# P2_2478.net
KiCad netlist of a schematic drawn in Altium Designer
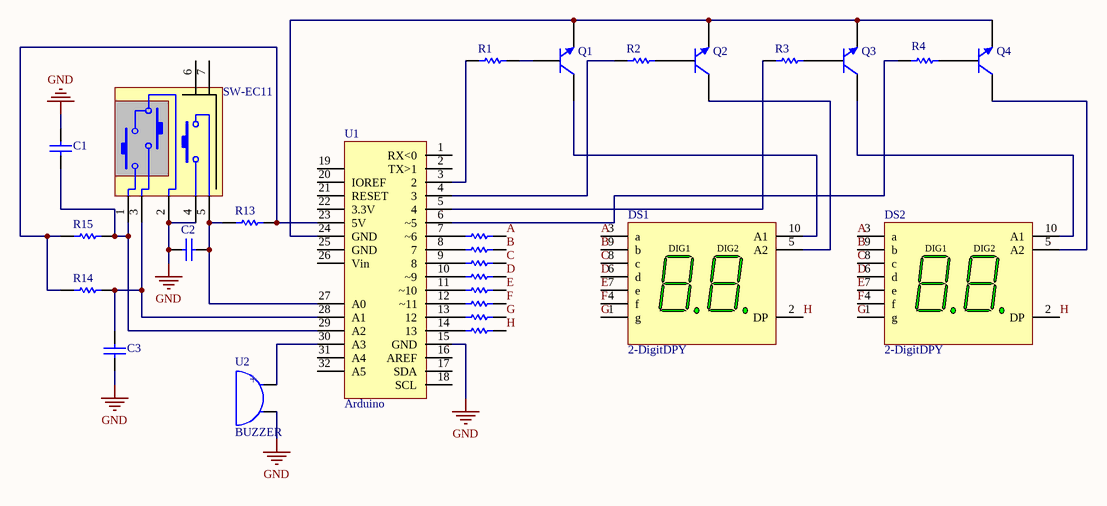
[diagram p0: P2_2478.SchDoc]

(export (version "E")
  (design (tool "Eeschema 10.0.6"))
  (components
    (comp (ref "C1")
      (value "Cap")
      (footprint "RAD-0.2")
      (description "Capacitor")
      (fields (field (name "PUBLISHER") "Altium Limited"))
      (libsource (lib "Miscellaneous Devices") (part "Cap"))
    )
    (comp (ref "C2")
      (value "Cap")
      (footprint "RAD-0.2")
      (description "Capacitor")
      (fields (field (name "PUBLISHER") "Altium Limited"))
      (libsource (lib "Miscellaneous Devices") (part "Cap"))
    )
    (comp (ref "C3")
      (value "Cap")
      (footprint "RAD-0.2")
      (description "Capacitor")
      (fields (field (name "PUBLISHER") "Altium Limited"))
      (libsource (lib "Miscellaneous Devices") (part "Cap"))
    )
    (comp (ref "DS1")
      (value "2-DigitDPY")
      (footprint "2-DigitDPY")
      (description "9.2 mm Green 7-Segment Display: 2-Digit, RH DP")
      (fields (field (name "PUBLISHER") "Altium Limited"))
      (libsource (lib "LixhSch") (part "2-DigitDPY"))
    )
    (comp (ref "DS2")
      (value "2-DigitDPY")
      (footprint "2-DigitDPY")
      (description "9.2 mm Green 7-Segment Display: 2-Digit, RH DP")
      (fields (field (name "PUBLISHER") "Altium Limited"))
      (libsource (lib "LixhSch") (part "2-DigitDPY"))
    )
    (comp (ref "Q1")
      (value "NPN")
      (footprint "TO-226")
      (description "NPN Bipolar Transistor")
      (fields (field (name "PUBLISHER") "Altium Limited"))
      (libsource (lib "Miscellaneous Devices") (part "NPN"))
    )
    (comp (ref "Q2")
      (value "NPN")
      (footprint "TO-226")
      (description "NPN Bipolar Transistor")
      (fields (field (name "PUBLISHER") "Altium Limited"))
      (libsource (lib "Miscellaneous Devices") (part "NPN"))
    )
    (comp (ref "Q3")
      (value "NPN")
      (footprint "TO-226")
      (description "NPN Bipolar Transistor")
      (fields (field (name "PUBLISHER") "Altium Limited"))
      (libsource (lib "Miscellaneous Devices") (part "NPN"))
    )
    (comp (ref "Q4")
      (value "NPN")
      (footprint "TO-226")
      (description "NPN Bipolar Transistor")
      (fields (field (name "PUBLISHER") "Altium Limited"))
      (libsource (lib "Miscellaneous Devices") (part "NPN"))
    )
    (comp (ref "R1")
      (value "Res1")
      (footprint "AXIAL-0.4")
      (description "Resistor")
      (fields (field (name "PUBLISHER") "Altium Limited"))
      (libsource (lib "Miscellaneous Devices") (part "Res1"))
    )
    (comp (ref "R2")
      (value "Res1")
      (footprint "AXIAL-0.4")
      (description "Resistor")
      (fields (field (name "PUBLISHER") "Altium Limited"))
      (libsource (lib "Miscellaneous Devices") (part "Res1"))
    )
    (comp (ref "R3")
      (value "Res1")
      (footprint "AXIAL-0.4")
      (description "Resistor")
      (fields (field (name "PUBLISHER") "Altium Limited"))
      (libsource (lib "Miscellaneous Devices") (part "Res1"))
    )
    (comp (ref "R4")
      (value "Res1")
      (footprint "AXIAL-0.4")
      (description "Resistor")
      (fields (field (name "PUBLISHER") "Altium Limited"))
      (libsource (lib "Miscellaneous Devices") (part "Res1"))
    )
    (comp (ref "R5")
      (value "Res1")
      (footprint "AXIAL-0.4")
      (description "Resistor")
      (fields (field (name "PUBLISHER") "Altium Limited"))
      (libsource (lib "Miscellaneous Devices") (part "Res1"))
    )
    (comp (ref "R6")
      (value "Res1")
      (footprint "AXIAL-0.4")
      (description "Resistor")
      (fields (field (name "PUBLISHER") "Altium Limited"))
      (libsource (lib "Miscellaneous Devices") (part "Res1"))
    )
    (comp (ref "R7")
      (value "Res1")
      (footprint "AXIAL-0.4")
      (description "Resistor")
      (fields (field (name "PUBLISHER") "Altium Limited"))
      (libsource (lib "Miscellaneous Devices") (part "Res1"))
    )
    (comp (ref "R8")
      (value "Res1")
      (footprint "AXIAL-0.4")
      (description "Resistor")
      (fields (field (name "PUBLISHER") "Altium Limited"))
      (libsource (lib "Miscellaneous Devices") (part "Res1"))
    )
    (comp (ref "R9")
      (value "Res1")
      (footprint "AXIAL-0.4")
      (description "Resistor")
      (fields (field (name "PUBLISHER") "Altium Limited"))
      (libsource (lib "Miscellaneous Devices") (part "Res1"))
    )
    (comp (ref "R10")
      (value "Res1")
      (footprint "AXIAL-0.4")
      (description "Resistor")
      (fields (field (name "PUBLISHER") "Altium Limited"))
      (libsource (lib "Miscellaneous Devices") (part "Res1"))
    )
    (comp (ref "R11")
      (value "Res1")
      (footprint "AXIAL-0.4")
      (description "Resistor")
      (fields (field (name "PUBLISHER") "Altium Limited"))
      (libsource (lib "Miscellaneous Devices") (part "Res1"))
    )
    (comp (ref "R12")
      (value "Res1")
      (footprint "AXIAL-0.4")
      (description "Resistor")
      (fields (field (name "PUBLISHER") "Altium Limited"))
      (libsource (lib "Miscellaneous Devices") (part "Res1"))
    )
    (comp (ref "R13")
      (value "Res1")
      (footprint "AXIAL-0.4")
      (description "Resistor")
      (fields (field (name "PUBLISHER") "Altium Limited"))
      (libsource (lib "Miscellaneous Devices") (part "Res1"))
    )
    (comp (ref "R14")
      (value "Res1")
      (footprint "AXIAL-0.4")
      (description "Resistor")
      (fields (field (name "PUBLISHER") "Altium Limited"))
      (libsource (lib "Miscellaneous Devices") (part "Res1"))
    )
    (comp (ref "R15")
      (value "Res1")
      (footprint "AXIAL-0.4")
      (description "Resistor")
      (fields (field (name "PUBLISHER") "Altium Limited"))
      (libsource (lib "Miscellaneous Devices") (part "Res1"))
    )
    (comp (ref "SW-EC11")
      (value "SW-EC11")
      (footprint "EC11")
      (description "旋转编码开关")
      (fields (field (name "PUBLISHER") "Altium Limited"))
      (libsource (lib "LixhSch") (part "SW-EC11"))
    )
    (comp (ref "U1")
      (value "Arduino")
      (footprint "Arduino-UNO")
      (libsource (lib "LixhSch") (part "Arduino-UNO"))
    )
    (comp (ref "U2")
      (value "BUZZER")
      (footprint "Buzzer")
      (description "Buzzer")
      (libsource (lib "Miscellaneous Devices") (part "BUZZER"))
    )
  )
  (nets
    (net (code "1") (name "/A") (class "Default")
      (node (ref "DS1") (pin "3") (pinfunction "a_3") (pintype "passive"))
      (node (ref "DS2") (pin "3") (pinfunction "a_3") (pintype "passive"))
      (node (ref "R5") (pin "2") (pinfunction "2_2") (pintype "passive"))
    )
    (net (code "2") (name "/B") (class "Default")
      (node (ref "DS1") (pin "9") (pinfunction "b_9") (pintype "passive"))
      (node (ref "DS2") (pin "9") (pinfunction "b_9") (pintype "passive"))
      (node (ref "R6") (pin "2") (pinfunction "2_2") (pintype "passive"))
    )
    (net (code "3") (name "/C") (class "Default")
      (node (ref "DS1") (pin "8") (pinfunction "c_8") (pintype "passive"))
      (node (ref "DS2") (pin "8") (pinfunction "c_8") (pintype "passive"))
      (node (ref "R7") (pin "2") (pinfunction "2_2") (pintype "passive"))
    )
    (net (code "4") (name "/D") (class "Default")
      (node (ref "DS1") (pin "6") (pinfunction "d_6") (pintype "passive"))
      (node (ref "DS2") (pin "6") (pinfunction "d_6") (pintype "passive"))
      (node (ref "R8") (pin "2") (pinfunction "2_2") (pintype "passive"))
    )
    (net (code "5") (name "/E") (class "Default")
      (node (ref "DS1") (pin "7") (pinfunction "e_7") (pintype "passive"))
      (node (ref "DS2") (pin "7") (pinfunction "e_7") (pintype "passive"))
      (node (ref "R9") (pin "2") (pinfunction "2_2") (pintype "passive"))
    )
    (net (code "6") (name "/F") (class "Default")
      (node (ref "DS1") (pin "4") (pinfunction "f_4") (pintype "passive"))
      (node (ref "DS2") (pin "4") (pinfunction "f_4") (pintype "passive"))
      (node (ref "R10") (pin "2") (pinfunction "2_2") (pintype "passive"))
    )
    (net (code "7") (name "/G") (class "Default")
      (node (ref "DS1") (pin "1") (pinfunction "g_1") (pintype "passive"))
      (node (ref "DS2") (pin "1") (pinfunction "g_1") (pintype "passive"))
      (node (ref "R11") (pin "2") (pinfunction "2_2") (pintype "passive"))
    )
    (net (code "8") (name "/H") (class "Default")
      (node (ref "DS1") (pin "2") (pinfunction "DP_2") (pintype "passive"))
      (node (ref "DS2") (pin "2") (pinfunction "DP_2") (pintype "passive"))
      (node (ref "R12") (pin "2") (pinfunction "2_2") (pintype "passive"))
    )
    (net (code "9") (name "GND") (class "Default")
      (node (ref "C1") (pin "2") (pinfunction "2_2") (pintype "passive"))
      (node (ref "C2") (pin "2") (pinfunction "2_2") (pintype "passive"))
      (node (ref "C3") (pin "2") (pinfunction "2_2") (pintype "passive"))
      (node (ref "SW-EC11") (pin "2") (pinfunction "2_2") (pintype "passive"))
      (node (ref "SW-EC11") (pin "4") (pinfunction "4_4") (pintype "passive"))
      (node (ref "U1") (pin "15") (pinfunction "GND_15") (pintype "power_in"))
      (node (ref "U2") (pin "2") (pinfunction "B_2") (pintype "passive"))
    )
    (net (code "10") (name "Net-(DS1-A1)") (class "Default")
      (node (ref "DS1") (pin "10") (pinfunction "A1_10") (pintype "passive"))
      (node (ref "Q1") (pin "1") (pinfunction "C_1") (pintype "passive"))
    )
    (net (code "11") (name "Net-(DS1-A2)") (class "Default")
      (node (ref "DS1") (pin "5") (pinfunction "A2_5") (pintype "passive"))
      (node (ref "Q2") (pin "1") (pinfunction "C_1") (pintype "passive"))
    )
    (net (code "12") (name "Net-(DS2-A1)") (class "Default")
      (node (ref "DS2") (pin "10") (pinfunction "A1_10") (pintype "passive"))
      (node (ref "Q3") (pin "1") (pinfunction "C_1") (pintype "passive"))
    )
    (net (code "13") (name "Net-(DS2-A2)") (class "Default")
      (node (ref "DS2") (pin "5") (pinfunction "A2_5") (pintype "passive"))
      (node (ref "Q4") (pin "1") (pinfunction "C_1") (pintype "passive"))
    )
    (net (code "14") (name "Net-(Q1-B)") (class "Default")
      (node (ref "Q1") (pin "2") (pinfunction "B_2") (pintype "passive"))
      (node (ref "R1") (pin "2") (pinfunction "2_2") (pintype "passive"))
    )
    (net (code "15") (name "Net-(Q1-E)") (class "Default")
      (node (ref "Q1") (pin "3") (pinfunction "E_3") (pintype "passive"))
      (node (ref "Q2") (pin "3") (pinfunction "E_3") (pintype "passive"))
      (node (ref "Q3") (pin "3") (pinfunction "E_3") (pintype "passive"))
      (node (ref "Q4") (pin "3") (pinfunction "E_3") (pintype "passive"))
      (node (ref "U1") (pin "24") (pinfunction "GND_24") (pintype "power_in"))
    )
    (net (code "16") (name "Net-(Q2-B)") (class "Default")
      (node (ref "Q2") (pin "2") (pinfunction "B_2") (pintype "passive"))
      (node (ref "R2") (pin "2") (pinfunction "2_2") (pintype "passive"))
    )
    (net (code "17") (name "Net-(Q3-B)") (class "Default")
      (node (ref "Q3") (pin "2") (pinfunction "B_2") (pintype "passive"))
      (node (ref "R3") (pin "2") (pinfunction "2_2") (pintype "passive"))
    )
    (net (code "18") (name "Net-(Q4-B)") (class "Default")
      (node (ref "Q4") (pin "2") (pinfunction "B_2") (pintype "passive"))
      (node (ref "R4") (pin "2") (pinfunction "2_2") (pintype "passive"))
    )
    (net (code "19") (name "Net-(U1-2)") (class "Default")
      (node (ref "R1") (pin "1") (pinfunction "1_1") (pintype "passive"))
      (node (ref "U1") (pin "3") (pinfunction "2_3") (pintype "power_in"))
    )
    (net (code "20") (name "Net-(U1-3)") (class "Default")
      (node (ref "R2") (pin "1") (pinfunction "1_1") (pintype "passive"))
      (node (ref "U1") (pin "4") (pinfunction "3_4") (pintype "power_in"))
    )
    (net (code "21") (name "Net-(U1-4)") (class "Default")
      (node (ref "R3") (pin "1") (pinfunction "1_1") (pintype "passive"))
      (node (ref "U1") (pin "5") (pinfunction "4_5") (pintype "power_in"))
    )
    (net (code "22") (name "Net-(U1-5V)") (class "Default")
      (node (ref "R13") (pin "2") (pinfunction "2_2") (pintype "passive"))
      (node (ref "R14") (pin "1") (pinfunction "1_1") (pintype "passive"))
      (node (ref "R15") (pin "1") (pinfunction "1_1") (pintype "passive"))
      (node (ref "U1") (pin "23") (pinfunction "5V_23") (pintype "power_in"))
    )
    (net (code "23") (name "Net-(U1-7)") (class "Default")
      (node (ref "R6") (pin "1") (pinfunction "1_1") (pintype "passive"))
      (node (ref "U1") (pin "8") (pinfunction "7_8") (pintype "power_in"))
    )
    (net (code "24") (name "Net-(U1-8)") (class "Default")
      (node (ref "R7") (pin "1") (pinfunction "1_1") (pintype "passive"))
      (node (ref "U1") (pin "9") (pinfunction "8_9") (pintype "power_in"))
    )
    (net (code "25") (name "Net-(U1-12)") (class "Default")
      (node (ref "R11") (pin "1") (pinfunction "1_1") (pintype "passive"))
      (node (ref "U1") (pin "13") (pinfunction "12_13") (pintype "power_in"))
    )
    (net (code "26") (name "Net-(U1-13)") (class "Default")
      (node (ref "R12") (pin "1") (pinfunction "1_1") (pintype "passive"))
      (node (ref "U1") (pin "14") (pinfunction "13_14") (pintype "power_in"))
    )
    (net (code "27") (name "Net-(U1-A0)") (class "Default")
      (node (ref "C2") (pin "1") (pinfunction "1_1") (pintype "passive"))
      (node (ref "R13") (pin "1") (pinfunction "1_1") (pintype "passive"))
      (node (ref "SW-EC11") (pin "5") (pinfunction "5_5") (pintype "passive"))
      (node (ref "U1") (pin "27") (pinfunction "A0_27") (pintype "power_in"))
    )
    (net (code "28") (name "Net-(U1-A1)") (class "Default")
      (node (ref "C3") (pin "1") (pinfunction "1_1") (pintype "passive"))
      (node (ref "R14") (pin "2") (pinfunction "2_2") (pintype "passive"))
      (node (ref "SW-EC11") (pin "3") (pinfunction "3_3") (pintype "passive"))
      (node (ref "U1") (pin "28") (pinfunction "A1_28") (pintype "power_in"))
    )
    (net (code "29") (name "Net-(U1-A2)") (class "Default")
      (node (ref "C1") (pin "1") (pinfunction "1_1") (pintype "passive"))
      (node (ref "R15") (pin "2") (pinfunction "2_2") (pintype "passive"))
      (node (ref "SW-EC11") (pin "1") (pinfunction "1_1") (pintype "passive"))
      (node (ref "U1") (pin "29") (pinfunction "A2_29") (pintype "power_in"))
    )
    (net (code "30") (name "Net-(U1-A3)") (class "Default")
      (node (ref "U1") (pin "30") (pinfunction "A3_30") (pintype "power_in"))
      (node (ref "U2") (pin "1") (pinfunction "A_1") (pintype "passive"))
    )
    (net (code "31") (name "Net-(U1-~5)") (class "Default")
      (node (ref "R4") (pin "1") (pinfunction "1_1") (pintype "passive"))
      (node (ref "U1") (pin "6") (pinfunction "~5_6") (pintype "power_in"))
    )
    (net (code "32") (name "Net-(U1-~6)") (class "Default")
      (node (ref "R5") (pin "1") (pinfunction "1_1") (pintype "passive"))
      (node (ref "U1") (pin "7") (pinfunction "~6_7") (pintype "power_in"))
    )
    (net (code "33") (name "Net-(U1-~9)") (class "Default")
      (node (ref "R8") (pin "1") (pinfunction "1_1") (pintype "passive"))
      (node (ref "U1") (pin "10") (pinfunction "~9_10") (pintype "power_in"))
    )
    (net (code "34") (name "Net-(U1-~10)") (class "Default")
      (node (ref "R9") (pin "1") (pinfunction "1_1") (pintype "passive"))
      (node (ref "U1") (pin "11") (pinfunction "~10_11") (pintype "power_in"))
    )
    (net (code "35") (name "Net-(U1-~11)") (class "Default")
      (node (ref "R10") (pin "1") (pinfunction "1_1") (pintype "passive"))
      (node (ref "U1") (pin "12") (pinfunction "~11_12") (pintype "power_in"))
    )
    (net (code "36") (name "unconnected-(SW-EC11-Pad6)") (class "Default")
      (node (ref "SW-EC11") (pin "6") (pinfunction "6_6") (pintype "passive"))
    )
    (net (code "37") (name "unconnected-(SW-EC11-Pad7)") (class "Default")
      (node (ref "SW-EC11") (pin "7") (pinfunction "7_7") (pintype "passive"))
    )
    (net (code "38") (name "unconnected-(U1-3.3V-Pad22)") (class "Default")
      (node (ref "U1") (pin "22") (pinfunction "3.3V_22") (pintype "power_in"))
    )
    (net (code "39") (name "unconnected-(U1-A4-Pad31)") (class "Default")
      (node (ref "U1") (pin "31") (pinfunction "A4_31") (pintype "power_in"))
    )
    (net (code "40") (name "unconnected-(U1-A5-Pad32)") (class "Default")
      (node (ref "U1") (pin "32") (pinfunction "A5_32") (pintype "power_in"))
    )
    (net (code "41") (name "unconnected-(U1-AREF-Pad16)") (class "Default")
      (node (ref "U1") (pin "16") (pinfunction "AREF_16") (pintype "power_in"))
    )
    (net (code "42") (name "unconnected-(U1-GND-Pad25)") (class "Default")
      (node (ref "U1") (pin "25") (pinfunction "GND_25") (pintype "power_in"))
    )
    (net (code "43") (name "unconnected-(U1-IOREF-Pad20)") (class "Default")
      (node (ref "U1") (pin "20") (pinfunction "IOREF_20") (pintype "power_in"))
    )
    (net (code "44") (name "unconnected-(U1-Pad19)") (class "Default")
      (node (ref "U1") (pin "19") (pintype "power_in"))
    )
    (net (code "45") (name "unconnected-(U1-RESET-Pad21)") (class "Default")
      (node (ref "U1") (pin "21") (pinfunction "RESET_21") (pintype "power_in"))
    )
    (net (code "46") (name "unconnected-(U1-RX<0-Pad1)") (class "Default")
      (node (ref "U1") (pin "1") (pinfunction "RX<0_1") (pintype "power_in"))
    )
    (net (code "47") (name "unconnected-(U1-SCL-Pad18)") (class "Default")
      (node (ref "U1") (pin "18") (pinfunction "SCL_18") (pintype "power_in"))
    )
    (net (code "48") (name "unconnected-(U1-SDA-Pad17)") (class "Default")
      (node (ref "U1") (pin "17") (pinfunction "SDA_17") (pintype "power_in"))
    )
    (net (code "49") (name "unconnected-(U1-TX>1-Pad2)") (class "Default")
      (node (ref "U1") (pin "2") (pinfunction "TX>1_2") (pintype "power_in"))
    )
    (net (code "50") (name "unconnected-(U1-Vin-Pad26)") (class "Default")
      (node (ref "U1") (pin "26") (pinfunction "Vin_26") (pintype "power_in"))
    )
  )
)
